# led_PA.net
KiCad netlist of a schematic drawn in Altium Designer
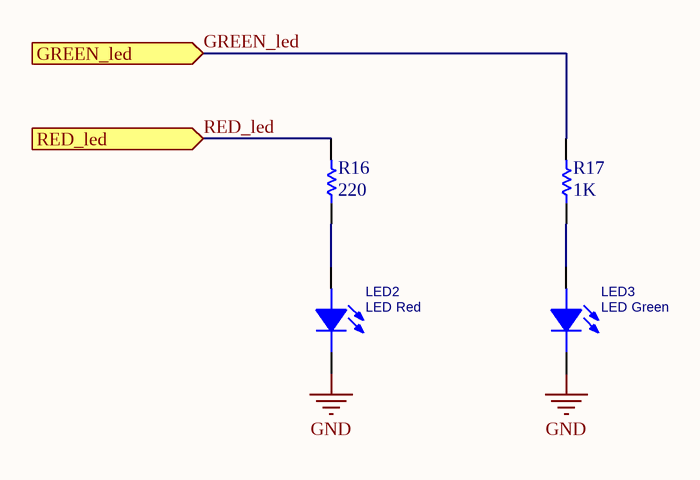
[diagram p0: led_PA.SchDoc]

(export (version "E")
  (design (tool "Eeschema 10.0.6"))
  (components
    (comp (ref "LED2")
      (value "LED Red")
      (footprint "led_0805")
      (description "Light Emitting Diode")
      (fields (field (name "DESIGNER") "Abbas Basereh"))
      (libsource (lib "Altium (2)") (part "LED 5MM"))
    )
    (comp (ref "LED3")
      (value "LED Green")
      (footprint "led_0805")
      (description "Light Emitting Diode")
      (fields (field (name "DESIGNER") "Abbas Basereh"))
      (libsource (lib "Altium (2)") (part "LED 5MM"))
    )
    (comp (ref "R16")
      (value "220")
      (footprint "RES 0805 (2012X06L)")
      (description "RES Axial 0.25W")
      (fields (field (name "DESIGNER") "Abbas Basereh"))
      (libsource (lib "Altium (2)") (part "RES Axial 0.25W"))
    )
    (comp (ref "R17")
      (value "1K")
      (footprint "RES 0805 (2012X06L)")
      (description "RES Axial 0.25W")
      (fields (field (name "DESIGNER") "Abbas Basereh"))
      (libsource (lib "Altium (2)") (part "RES Axial 0.25W"))
    )
  )
  (nets
    (net (code "1") (name "/GREEN_led") (class "Default")
      (node (ref "R17") (pin "2") (pinfunction "2_2") (pintype "passive"))
    )
    (net (code "2") (name "/RED_led") (class "Default")
      (node (ref "R16") (pin "2") (pinfunction "2_2") (pintype "passive"))
    )
    (net (code "3") (name "GND") (class "Default")
      (node (ref "LED2") (pin "2") (pinfunction "CATHODE_2") (pintype "passive"))
      (node (ref "LED3") (pin "2") (pinfunction "CATHODE_2") (pintype "passive"))
    )
    (net (code "4") (name "Net-(LED2-ANODE)") (class "Default")
      (node (ref "LED2") (pin "1") (pinfunction "ANODE_1") (pintype "passive"))
      (node (ref "R16") (pin "1") (pinfunction "1_1") (pintype "passive"))
    )
    (net (code "5") (name "Net-(LED3-ANODE)") (class "Default")
      (node (ref "LED3") (pin "1") (pinfunction "ANODE_1") (pintype "passive"))
      (node (ref "R17") (pin "1") (pinfunction "1_1") (pintype "passive"))
    )
  )
)
